# amp_test_filter_variable.net
KiCad netlist of a schematic drawn in EAGLE
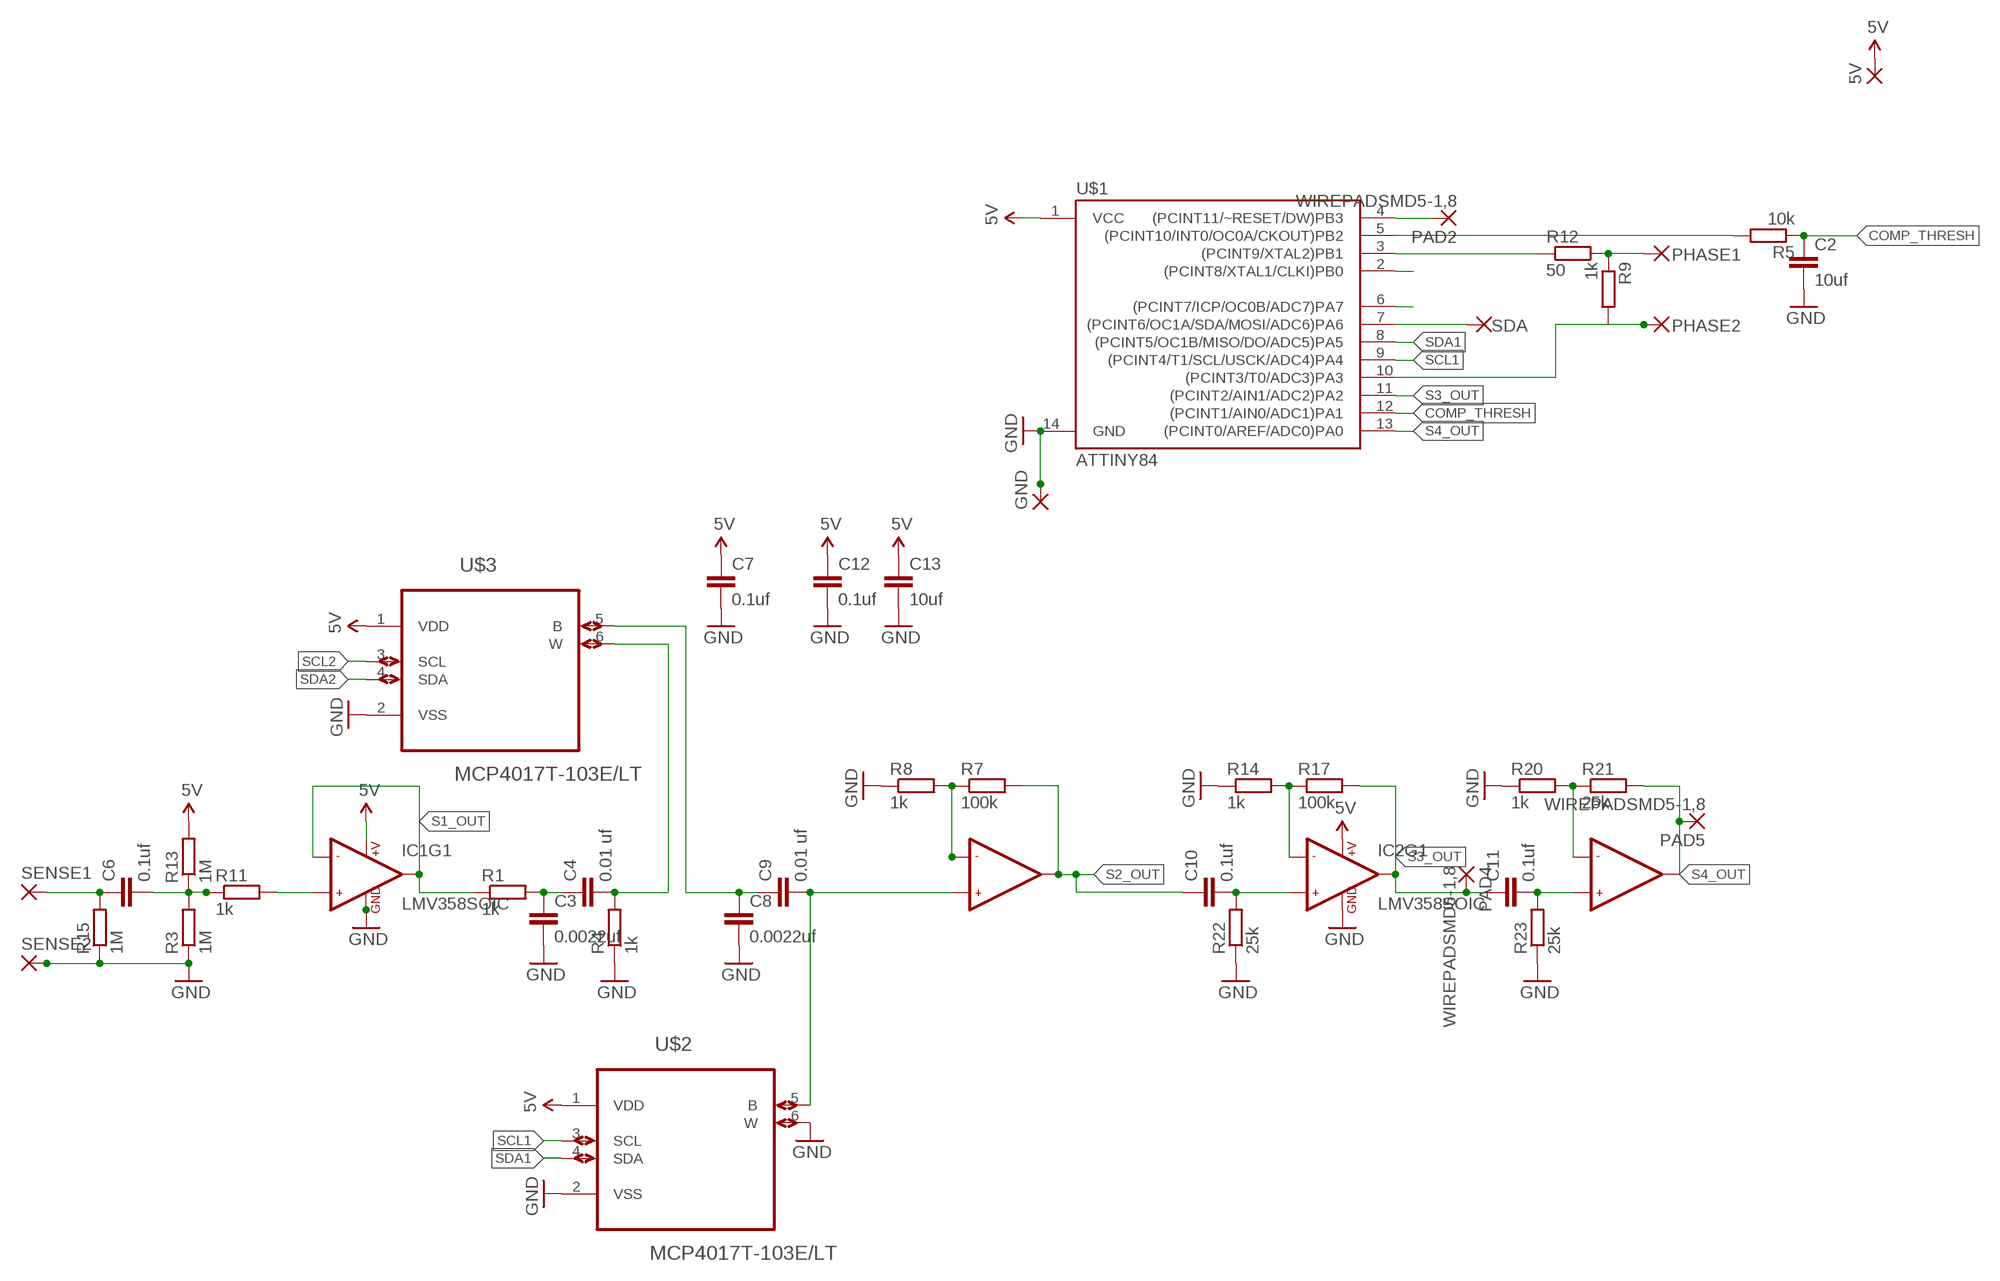
[diagram p0: schematic, sheet 1]

(export (version "E")
  (design (tool "Eeschema 10.0.6"))
  (components
    (comp (ref "5V")
      (value "SMD5")
      (footprint "eagle-import:SMD2,54-5,08")
      (libsource (lib "eagle-import") (part "SMD5"))
    )
    (comp (ref "C2")
      (value "10uf")
      (footprint "eagle-import:C0603")
      (libsource (lib "eagle-import") (part "C-EUC0603"))
    )
    (comp (ref "C3")
      (value "0.0022uf")
      (footprint "eagle-import:C0603")
      (libsource (lib "eagle-import") (part "C-EUC0603"))
    )
    (comp (ref "C4")
      (value "0.01 uf")
      (footprint "eagle-import:C0603")
      (libsource (lib "eagle-import") (part "C-EUC0603"))
    )
    (comp (ref "C6")
      (value "0.1uf")
      (footprint "eagle-import:C0603")
      (libsource (lib "eagle-import") (part "C-EUC0603"))
    )
    (comp (ref "C7")
      (value "0.1uf")
      (footprint "eagle-import:C0603")
      (libsource (lib "eagle-import") (part "C-EUC0603"))
    )
    (comp (ref "C8")
      (value "0.0022uf")
      (footprint "eagle-import:C0603")
      (libsource (lib "eagle-import") (part "C-EUC0603"))
    )
    (comp (ref "C9")
      (value "0.01 uf")
      (footprint "eagle-import:C0603")
      (libsource (lib "eagle-import") (part "C-EUC0603"))
    )
    (comp (ref "C10")
      (value "0.1uf")
      (footprint "eagle-import:C0603")
      (libsource (lib "eagle-import") (part "C-EUC0603"))
    )
    (comp (ref "C11")
      (value "0.1uf")
      (footprint "eagle-import:C0603")
      (libsource (lib "eagle-import") (part "C-EUC0603"))
    )
    (comp (ref "C12")
      (value "0.1uf")
      (footprint "eagle-import:C0603")
      (libsource (lib "eagle-import") (part "C-EUC0603"))
    )
    (comp (ref "C13")
      (value "10uf")
      (footprint "eagle-import:C0603")
      (libsource (lib "eagle-import") (part "C-EUC0603"))
    )
    (comp (ref "GND")
      (value "SMD5")
      (footprint "eagle-import:SMD2,54-5,08")
      (libsource (lib "eagle-import") (part "SMD5"))
    )
    (comp (ref "IC1")
      (value "LMV358SOIC")
      (footprint "eagle-import:SO08")
      (libsource (lib "eagle-import") (part "LMV358SOIC"))
    )
    (comp (ref "IC2")
      (value "LMV358SOIC")
      (footprint "eagle-import:SO08")
      (libsource (lib "eagle-import") (part "LMV358SOIC"))
    )
    (comp (ref "PAD2")
      (value "WIREPADSMD5-1,8")
      (footprint "eagle-import:5-1,8")
      (libsource (lib "eagle-import") (part "WIREPADSMD5-1,8"))
    )
    (comp (ref "PAD4")
      (value "WIREPADSMD5-1,8")
      (footprint "eagle-import:5-1,8")
      (libsource (lib "eagle-import") (part "WIREPADSMD5-1,8"))
    )
    (comp (ref "PAD5")
      (value "WIREPADSMD5-1,8")
      (footprint "eagle-import:5-1,8")
      (libsource (lib "eagle-import") (part "WIREPADSMD5-1,8"))
    )
    (comp (ref "PHASE1")
      (value "SMD5")
      (footprint "eagle-import:SMD2,54-5,08")
      (libsource (lib "eagle-import") (part "SMD5"))
    )
    (comp (ref "PHASE2")
      (value "SMD5")
      (footprint "eagle-import:SMD2,54-5,08")
      (libsource (lib "eagle-import") (part "SMD5"))
    )
    (comp (ref "R1")
      (value "1k")
      (footprint "eagle-import:R0603")
      (libsource (lib "eagle-import") (part "R-EU_R0603"))
    )
    (comp (ref "R3")
      (value "1M")
      (footprint "eagle-import:R0603")
      (libsource (lib "eagle-import") (part "R-EU_R0603"))
    )
    (comp (ref "R4")
      (value "1k")
      (footprint "eagle-import:R0603")
      (libsource (lib "eagle-import") (part "R-EU_R0603"))
    )
    (comp (ref "R5")
      (value "10k")
      (footprint "eagle-import:R0603")
      (libsource (lib "eagle-import") (part "R-EU_R0603"))
    )
    (comp (ref "R7")
      (value "100k")
      (footprint "eagle-import:R0603")
      (libsource (lib "eagle-import") (part "R-EU_R0603"))
    )
    (comp (ref "R8")
      (value "1k")
      (footprint "eagle-import:R0603")
      (libsource (lib "eagle-import") (part "R-EU_R0603"))
    )
    (comp (ref "R9")
      (value "1k")
      (footprint "eagle-import:R0603")
      (libsource (lib "eagle-import") (part "R-EU_R0603"))
    )
    (comp (ref "R11")
      (value "1k")
      (footprint "eagle-import:R0603")
      (libsource (lib "eagle-import") (part "R-EU_R0603"))
    )
    (comp (ref "R12")
      (value "50")
      (footprint "eagle-import:R0603")
      (libsource (lib "eagle-import") (part "R-EU_R0603"))
    )
    (comp (ref "R13")
      (value "1M")
      (footprint "eagle-import:R0603")
      (libsource (lib "eagle-import") (part "R-EU_R0603"))
    )
    (comp (ref "R14")
      (value "1k")
      (footprint "eagle-import:R0603")
      (libsource (lib "eagle-import") (part "R-EU_R0603"))
    )
    (comp (ref "R15")
      (value "1M")
      (footprint "eagle-import:R0603")
      (libsource (lib "eagle-import") (part "R-EU_R0603"))
    )
    (comp (ref "R17")
      (value "100k")
      (footprint "eagle-import:R0603")
      (libsource (lib "eagle-import") (part "R-EU_R0603"))
    )
    (comp (ref "R20")
      (value "1k")
      (footprint "eagle-import:R0603")
      (libsource (lib "eagle-import") (part "R-EU_R0603"))
    )
    (comp (ref "R21")
      (value "25k")
      (footprint "eagle-import:R0603")
      (libsource (lib "eagle-import") (part "R-EU_R0603"))
    )
    (comp (ref "R22")
      (value "25k")
      (footprint "eagle-import:R0603")
      (libsource (lib "eagle-import") (part "R-EU_R0603"))
    )
    (comp (ref "R23")
      (value "25k")
      (footprint "eagle-import:R0603")
      (libsource (lib "eagle-import") (part "R-EU_R0603"))
    )
    (comp (ref "SDA")
      (value "SMD5")
      (footprint "eagle-import:SMD2,54-5,08")
      (libsource (lib "eagle-import") (part "SMD5"))
    )
    (comp (ref "SENSE1")
      (value "SMD5")
      (footprint "eagle-import:SMD2,54-5,08")
      (libsource (lib "eagle-import") (part "SMD5"))
    )
    (comp (ref "SENSE2")
      (value "SMD5")
      (footprint "eagle-import:SMD2,54-5,08")
      (libsource (lib "eagle-import") (part "SMD5"))
    )
    (comp (ref "U$1")
      (value "ATTINY84")
      (footprint "eagle-import:SO14")
      (libsource (lib "eagle-import") (part "ATTINY84"))
    )
    (comp (ref "U$2")
      (value "MCP4017T-103E/LT")
      (footprint "eagle-import:SOT65P210X110-6N")
      (fields (field (name "MF") "Microchip"))
      (libsource (lib "eagle-import") (part "MCP4017T-103E/LT"))
    )
    (comp (ref "U$3")
      (value "MCP4017T-103E/LT")
      (footprint "eagle-import:SOT65P210X110-6N")
      (fields (field (name "MF") "Microchip"))
      (libsource (lib "eagle-import") (part "MCP4017T-103E/LT"))
    )
  )
  (nets
    (net (code "1") (name "5V") (class "Default")
      (node (ref "5V") (pin "1") (pinfunction "P_1") (pintype "passive"))
      (node (ref "C12") (pin "1") (pinfunction "1_1") (pintype "passive"))
      (node (ref "C13") (pin "1") (pinfunction "1_1") (pintype "passive"))
      (node (ref "C7") (pin "1") (pinfunction "1_1") (pintype "passive"))
      (node (ref "IC1") (pin "8") (pinfunction "+V_8") (pintype "power_in"))
      (node (ref "IC2") (pin "8") (pinfunction "+V_8") (pintype "power_in"))
      (node (ref "R13") (pin "2") (pinfunction "2_2") (pintype "passive"))
      (node (ref "U$1") (pin "1") (pinfunction "VCC_1") (pintype "bidirectional"))
      (node (ref "U$2") (pin "1") (pinfunction "VDD_1") (pintype "power_in"))
      (node (ref "U$3") (pin "1") (pinfunction "VDD_1") (pintype "power_in"))
    )
    (net (code "2") (name "COMP_THRESH") (class "Default")
      (node (ref "C2") (pin "1") (pinfunction "1_1") (pintype "passive"))
      (node (ref "R5") (pin "1") (pinfunction "1_1") (pintype "passive"))
      (node (ref "U$1") (pin "12") (pinfunction "(PCINT1/AIN0/ADC1)PA1_12") (pintype "bidirectional"))
    )
    (net (code "3") (name "GND") (class "Default")
      (node (ref "C12") (pin "2") (pinfunction "2_2") (pintype "passive"))
      (node (ref "C13") (pin "2") (pinfunction "2_2") (pintype "passive"))
      (node (ref "C2") (pin "2") (pinfunction "2_2") (pintype "passive"))
      (node (ref "C3") (pin "2") (pinfunction "2_2") (pintype "passive"))
      (node (ref "C7") (pin "2") (pinfunction "2_2") (pintype "passive"))
      (node (ref "C8") (pin "2") (pinfunction "2_2") (pintype "passive"))
      (node (ref "GND") (pin "1") (pinfunction "P_1") (pintype "passive"))
      (node (ref "IC1") (pin "4") (pinfunction "GND_4") (pintype "power_in"))
      (node (ref "IC2") (pin "4") (pinfunction "GND_4") (pintype "power_in"))
      (node (ref "R14") (pin "1") (pinfunction "1_1") (pintype "passive"))
      (node (ref "R15") (pin "1") (pinfunction "1_1") (pintype "passive"))
      (node (ref "R20") (pin "1") (pinfunction "1_1") (pintype "passive"))
      (node (ref "R22") (pin "1") (pinfunction "1_1") (pintype "passive"))
      (node (ref "R23") (pin "1") (pinfunction "1_1") (pintype "passive"))
      (node (ref "R3") (pin "1") (pinfunction "1_1") (pintype "passive"))
      (node (ref "R4") (pin "1") (pinfunction "1_1") (pintype "passive"))
      (node (ref "R8") (pin "1") (pinfunction "1_1") (pintype "passive"))
      (node (ref "SENSE2") (pin "1") (pinfunction "P_1") (pintype "passive"))
      (node (ref "U$1") (pin "14") (pinfunction "GND_14") (pintype "bidirectional"))
      (node (ref "U$2") (pin "2") (pinfunction "VSS_2") (pintype "power_in"))
      (node (ref "U$2") (pin "6") (pinfunction "W_6") (pintype "bidirectional"))
      (node (ref "U$3") (pin "2") (pinfunction "VSS_2") (pintype "power_in"))
    )
    (net (code "4") (name "Net-(C3-Pad1)") (class "Default")
      (node (ref "C3") (pin "1") (pinfunction "1_1") (pintype "passive"))
      (node (ref "C4") (pin "1") (pinfunction "1_1") (pintype "passive"))
      (node (ref "R1") (pin "2") (pinfunction "2_2") (pintype "passive"))
    )
    (net (code "5") (name "Net-(C6-Pad2)") (class "Default")
      (node (ref "C6") (pin "2") (pinfunction "2_2") (pintype "passive"))
      (node (ref "R11") (pin "1") (pinfunction "1_1") (pintype "passive"))
      (node (ref "R13") (pin "1") (pinfunction "1_1") (pintype "passive"))
      (node (ref "R3") (pin "2") (pinfunction "2_2") (pintype "passive"))
    )
    (net (code "6") (name "Net-(IC1A-+IN1)") (class "Default")
      (node (ref "IC1") (pin "3") (pinfunction "+IN1_3") (pintype "input"))
      (node (ref "R11") (pin "2") (pinfunction "2_2") (pintype "passive"))
    )
    (net (code "7") (name "Net-(IC1B-+IN2)") (class "Default")
      (node (ref "C9") (pin "2") (pinfunction "2_2") (pintype "passive"))
      (node (ref "IC1") (pin "5") (pinfunction "+IN2_5") (pintype "input"))
      (node (ref "U$2") (pin "5") (pinfunction "B_5") (pintype "bidirectional"))
    )
    (net (code "8") (name "Net-(IC1B--IN2)") (class "Default")
      (node (ref "IC1") (pin "6") (pinfunction "-IN2_6") (pintype "input"))
      (node (ref "R7") (pin "1") (pinfunction "1_1") (pintype "passive"))
      (node (ref "R8") (pin "2") (pinfunction "2_2") (pintype "passive"))
    )
    (net (code "9") (name "Net-(IC2A-+IN1)") (class "Default")
      (node (ref "C10") (pin "2") (pinfunction "2_2") (pintype "passive"))
      (node (ref "IC2") (pin "3") (pinfunction "+IN1_3") (pintype "input"))
      (node (ref "R22") (pin "2") (pinfunction "2_2") (pintype "passive"))
    )
    (net (code "10") (name "Net-(IC2A--IN1)") (class "Default")
      (node (ref "IC2") (pin "2") (pinfunction "-IN1_2") (pintype "input"))
      (node (ref "R14") (pin "2") (pinfunction "2_2") (pintype "passive"))
      (node (ref "R17") (pin "1") (pinfunction "1_1") (pintype "passive"))
    )
    (net (code "11") (name "Net-(IC2B-+IN2)") (class "Default")
      (node (ref "C11") (pin "2") (pinfunction "2_2") (pintype "passive"))
      (node (ref "IC2") (pin "5") (pinfunction "+IN2_5") (pintype "input"))
      (node (ref "R23") (pin "2") (pinfunction "2_2") (pintype "passive"))
    )
    (net (code "12") (name "Net-(IC2B--IN2)") (class "Default")
      (node (ref "IC2") (pin "6") (pinfunction "-IN2_6") (pintype "input"))
      (node (ref "R20") (pin "2") (pinfunction "2_2") (pintype "passive"))
      (node (ref "R21") (pin "1") (pinfunction "1_1") (pintype "passive"))
    )
    (net (code "13") (name "Net-(PAD2-P)") (class "Default")
      (node (ref "PAD2") (pin "1") (pinfunction "P_1") (pintype "passive"))
      (node (ref "U$1") (pin "4") (pinfunction "(PCINT11/~{RESET/DW})PB3_4") (pintype "bidirectional"))
    )
    (net (code "14") (name "Net-(PHASE1-P)") (class "Default")
      (node (ref "PHASE1") (pin "1") (pinfunction "P_1") (pintype "passive"))
      (node (ref "R12") (pin "2") (pinfunction "2_2") (pintype "passive"))
      (node (ref "R9") (pin "1") (pinfunction "1_1") (pintype "passive"))
    )
    (net (code "15") (name "Net-(PHASE2-P)") (class "Default")
      (node (ref "PHASE2") (pin "1") (pinfunction "P_1") (pintype "passive"))
      (node (ref "R9") (pin "2") (pinfunction "2_2") (pintype "passive"))
      (node (ref "U$1") (pin "10") (pinfunction "(PCINT3/T0/ADC3)PA3_10") (pintype "bidirectional"))
    )
    (net (code "16") (name "Net-(SDA-P)") (class "Default")
      (node (ref "SDA") (pin "1") (pinfunction "P_1") (pintype "passive"))
      (node (ref "U$1") (pin "7") (pinfunction "(PCINT6/OC1A/SDA/MOSI/ADC6)PA6_7") (pintype "bidirectional"))
    )
    (net (code "17") (name "Net-(SENSE1-P)") (class "Default")
      (node (ref "C6") (pin "1") (pinfunction "1_1") (pintype "passive"))
      (node (ref "R15") (pin "2") (pinfunction "2_2") (pintype "passive"))
      (node (ref "SENSE1") (pin "1") (pinfunction "P_1") (pintype "passive"))
    )
    (net (code "18") (name "Net-(U$1-(PCINT9{slash}XTAL2)PB1)") (class "Default")
      (node (ref "R12") (pin "1") (pinfunction "1_1") (pintype "passive"))
      (node (ref "U$1") (pin "3") (pinfunction "(PCINT9/XTAL2)PB1_3") (pintype "bidirectional"))
    )
    (net (code "19") (name "Net-(U$1-(PCINT10{slash}INT0{slash}OC0A{slash}CKOUT)PB2)") (class "Default")
      (node (ref "R5") (pin "2") (pinfunction "2_2") (pintype "passive"))
      (node (ref "U$1") (pin "5") (pinfunction "(PCINT10/INT0/OC0A/CKOUT)PB2_5") (pintype "bidirectional"))
    )
    (net (code "20") (name "Net-(U$3-B)") (class "Default")
      (node (ref "C8") (pin "1") (pinfunction "1_1") (pintype "passive"))
      (node (ref "C9") (pin "1") (pinfunction "1_1") (pintype "passive"))
      (node (ref "U$3") (pin "5") (pinfunction "B_5") (pintype "bidirectional"))
    )
    (net (code "21") (name "Net-(U$3-W)") (class "Default")
      (node (ref "C4") (pin "2") (pinfunction "2_2") (pintype "passive"))
      (node (ref "R4") (pin "2") (pinfunction "2_2") (pintype "passive"))
      (node (ref "U$3") (pin "6") (pinfunction "W_6") (pintype "bidirectional"))
    )
    (net (code "22") (name "S1_OUT") (class "Default")
      (node (ref "IC1") (pin "1") (pinfunction "OUT1_1") (pintype "output"))
      (node (ref "IC1") (pin "2") (pinfunction "-IN1_2") (pintype "input"))
      (node (ref "R1") (pin "1") (pinfunction "1_1") (pintype "passive"))
    )
    (net (code "23") (name "S2_OUT") (class "Default")
      (node (ref "C10") (pin "1") (pinfunction "1_1") (pintype "passive"))
      (node (ref "IC1") (pin "7") (pinfunction "OUT2_7") (pintype "output"))
      (node (ref "R7") (pin "2") (pinfunction "2_2") (pintype "passive"))
    )
    (net (code "24") (name "S3_OUT") (class "Default")
      (node (ref "C11") (pin "1") (pinfunction "1_1") (pintype "passive"))
      (node (ref "IC2") (pin "1") (pinfunction "OUT1_1") (pintype "output"))
      (node (ref "PAD4") (pin "1") (pinfunction "P_1") (pintype "passive"))
      (node (ref "R17") (pin "2") (pinfunction "2_2") (pintype "passive"))
      (node (ref "U$1") (pin "11") (pinfunction "(PCINT2/AIN1/ADC2)PA2_11") (pintype "bidirectional"))
    )
    (net (code "25") (name "S4_OUT") (class "Default")
      (node (ref "IC2") (pin "7") (pinfunction "OUT2_7") (pintype "output"))
      (node (ref "PAD5") (pin "1") (pinfunction "P_1") (pintype "passive"))
      (node (ref "R21") (pin "2") (pinfunction "2_2") (pintype "passive"))
      (node (ref "U$1") (pin "13") (pinfunction "(PCINT0/AREF/ADC0)PA0_13") (pintype "bidirectional"))
    )
    (net (code "26") (name "SCL1") (class "Default")
      (node (ref "U$1") (pin "9") (pinfunction "(PCINT4/T1/SCL/USCK/ADC4)PA4_9") (pintype "bidirectional"))
      (node (ref "U$2") (pin "3") (pinfunction "SCL_3") (pintype "bidirectional"))
    )
    (net (code "27") (name "SCL2") (class "Default")
      (node (ref "U$1") (pin "2") (pinfunction "(PCINT8/XTAL1/CLKI)PB0_2") (pintype "bidirectional"))
      (node (ref "U$3") (pin "3") (pinfunction "SCL_3") (pintype "bidirectional"))
    )
    (net (code "28") (name "SDA1") (class "Default")
      (node (ref "U$1") (pin "8") (pinfunction "(PCINT5/OC1B/MISO/DO/ADC5)PA5_8") (pintype "bidirectional"))
      (node (ref "U$2") (pin "4") (pinfunction "SDA_4") (pintype "bidirectional"))
    )
    (net (code "29") (name "SDA2") (class "Default")
      (node (ref "U$1") (pin "6") (pinfunction "(PCINT7/ICP/OC0B/ADC7)PA7_6") (pintype "bidirectional"))
      (node (ref "U$3") (pin "4") (pinfunction "SDA_4") (pintype "bidirectional"))
    )
  )
)
